# saw.net
KiCad netlist of a schematic drawn in Altium Designer
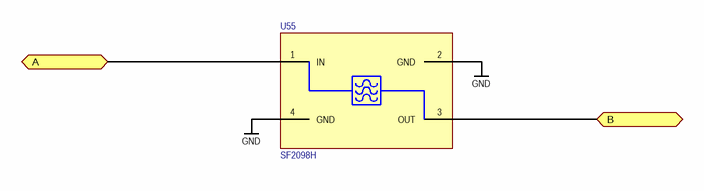
[diagram p0: saw.SchDoc]

(export (version "E")
  (design (tool "Eeschema 10.0.6"))
  (components
    (comp (ref "U55")
      (value "SF2098H")
      (footprint "rfm:SM2016-4")
      (description "915 MHz SAW Filter")
      (fields (field (name "MANUFACTURER") "RFM"))
      (libsource (lib "rfm") (part "SF2098H"))
    )
  )
  (nets
    (net (code "1") (name "/A") (class "Default")
      (node (ref "U55") (pin "1") (pinfunction "IN_1") (pintype "passive"))
    )
    (net (code "2") (name "/B") (class "Default")
      (node (ref "U55") (pin "3") (pinfunction "OUT_3") (pintype "passive"))
    )
    (net (code "3") (name "GND") (class "Default")
      (node (ref "U55") (pin "2") (pinfunction "GND_2") (pintype "passive"))
      (node (ref "U55") (pin "4") (pinfunction "GND_4") (pintype "passive"))
    )
  )
)
